# Thermal_MGT.net
KiCad netlist of a schematic drawn in Altium Designer
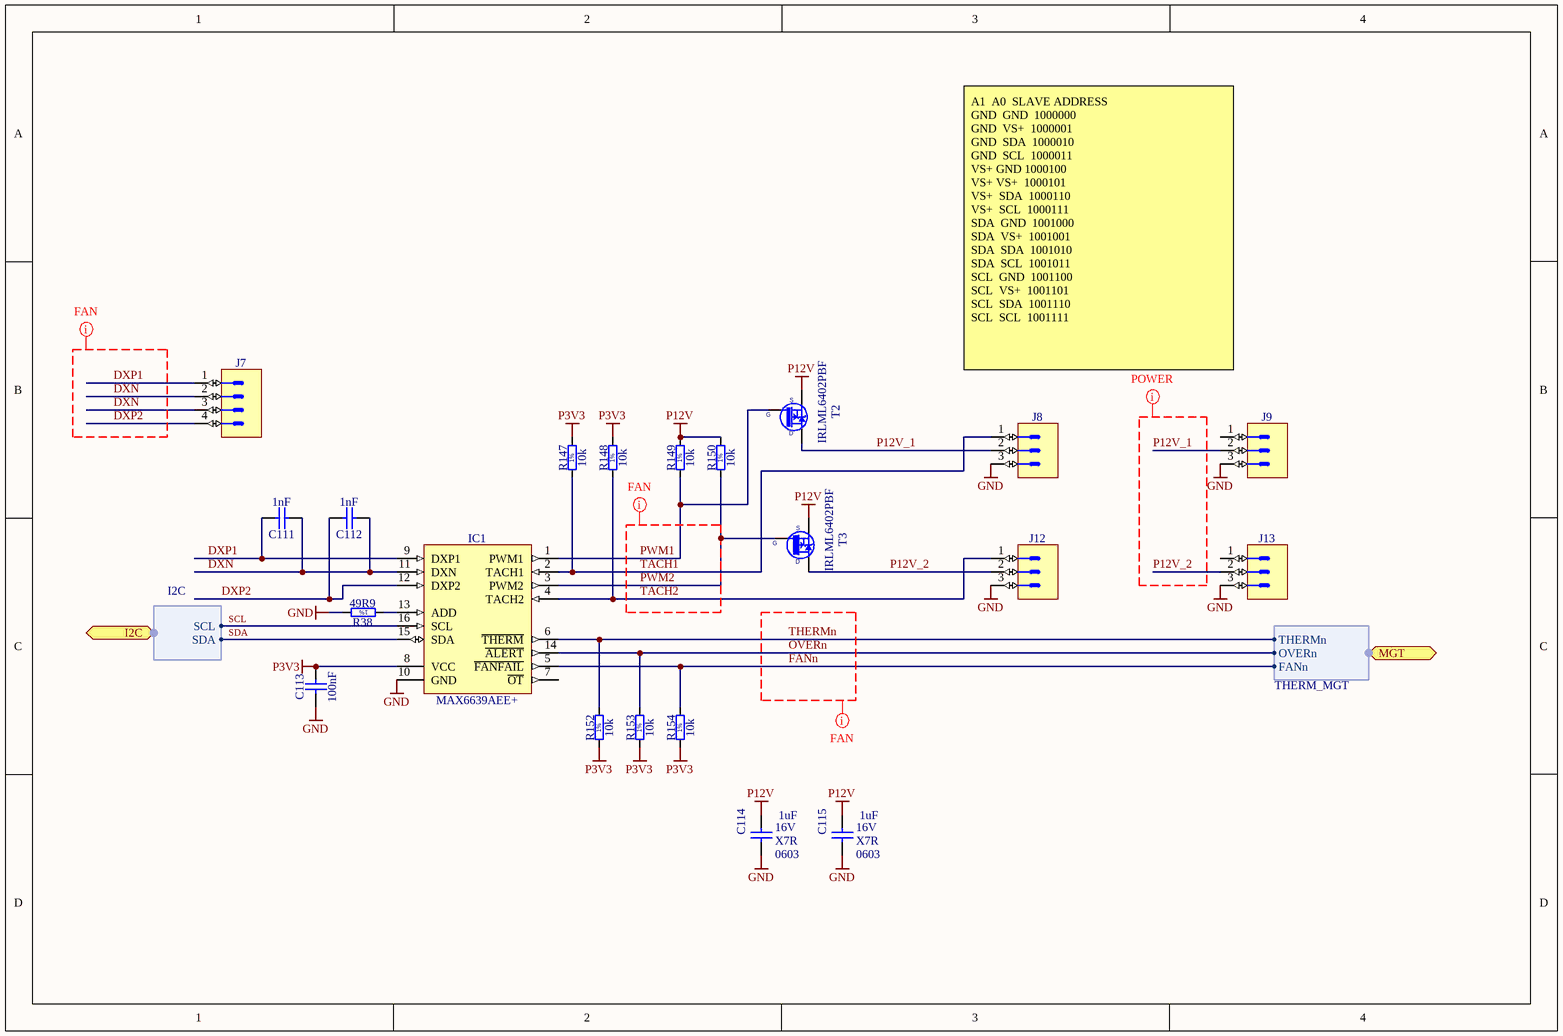
[diagram p0: Thermal_MGT.SchDoc]

(export (version "E")
  (design (tool "Eeschema 10.0.6"))
  (components
    (comp (ref "C111")
      (value "1nF")
      (footprint "CAPC1005X55N")
      (description "Non-polarised capacitor")
      (fields
        (field (name "PART NUMBER") "CC0402_1NF_50V_10%_X7R")
        (field (name "VOLTAGE") "50V")
        (field (name "AUTHOR") "CERN DEM JLC")
      )
      (libsource (lib "Capacitors") (part "Capacitor - non polarized"))
    )
    (comp (ref "C112")
      (value "1nF")
      (footprint "CAPC1005X55N")
      (description "Non-polarised capacitor")
      (fields
        (field (name "PART NUMBER") "CC0402_1NF_50V_10%_X7R")
        (field (name "VOLTAGE") "50V")
        (field (name "AUTHOR") "CERN DEM JLC")
      )
      (libsource (lib "Capacitors") (part "Capacitor - non polarized"))
    )
    (comp (ref "C113")
      (value "100nF")
      (footprint "CAPC1005X55N")
      (description "Non-polarised capacitor")
      (fields
        (field (name "PART NUMBER") "CC0402_100NF_16V_10%_X5R")
        (field (name "VOLTAGE") "16V")
        (field (name "AUTHOR") "CERN DEM JLC")
      )
      (libsource (lib "Capacitors") (part "Capacitor - non polarized"))
    )
    (comp (ref "C114")
      (value "1uF")
      (footprint "CAPC1608X87N")
      (description "Non-polarised capacitor")
      (fields
        (field (name "PART NUMBER") "CC0603_1UF_16V_10%_X7R")
        (field (name "VOLTAGE") "16V")
        (field (name "TC") "X7R")
        (field (name "TOLERANCE") "±10%")
        (field (name "CASE") "0603")
        (field (name "AUTHOR") "CERN DEM JLC")
      )
      (libsource (lib "Capacitors") (part "Capacitor - non polarized"))
    )
    (comp (ref "C115")
      (value "1uF")
      (footprint "CAPC1608X87N")
      (description "Non-polarised capacitor")
      (fields
        (field (name "PART NUMBER") "CC0603_1UF_16V_10%_X7R")
        (field (name "VOLTAGE") "16V")
        (field (name "TC") "X7R")
        (field (name "TOLERANCE") "±10%")
        (field (name "CASE") "0603")
        (field (name "AUTHOR") "CERN DEM JLC")
      )
      (libsource (lib "Capacitors") (part "Capacitor - non polarized"))
    )
    (comp (ref "IC1")
      (value "MAX6639AEE+")
      (footprint "SOP63P600X175-16N")
      (description "2-Channel Temperature Monitor with Dual, Automatic, PWM Fan-Speed Controller")
      (fields (field (name "MANUFACTURER") "MAXIM") (field (name "AUTHOR") "CERN DEM JLC"))
      (libsource (lib "ICs And Semiconductors") (part "MAX6639AEE+"))
    )
    (comp (ref "J7")
      (value "KK®")
      (footprint "MOLEX_22-27-2041")
      (description "Connector 4 Male")
      (fields
        (field (name "PART NUMBER") "MOLEX_22-27-2041")
        (field (name "MANUFACTURER") "MOLEX")
        (field (name "AUTHOR") "CERN DEM JLC")
      )
      (libsource (lib "Connectors") (part "Connector 4 Male"))
    )
    (comp (ref "J8")
      (value "KK®")
      (footprint "MOLEX_22-05-7038")
      (description "Connector 3 Male")
      (fields
        (field (name "PART NUMBER") "MOLEX_22-05-7038")
        (field (name "MANUFACTURER") "MOLEX")
        (field (name "AUTHOR") "CERN DEM JLC")
      )
      (libsource (lib "Connectors") (part "Connector 3 Male"))
    )
    (comp (ref "J9")
      (value "KK®")
      (footprint "MOLEX_22-05-7038")
      (description "Connector 3 Male")
      (fields
        (field (name "PART NUMBER") "MOLEX_22-05-7038")
        (field (name "MANUFACTURER") "MOLEX")
        (field (name "AUTHOR") "CERN DEM JLC")
      )
      (libsource (lib "Connectors") (part "Connector 3 Male"))
    )
    (comp (ref "J12")
      (value "KK®")
      (footprint "MOLEX_22-05-7038")
      (description "Connector 3 Male")
      (fields
        (field (name "PART NUMBER") "MOLEX_22-05-7038")
        (field (name "MANUFACTURER") "MOLEX")
        (field (name "AUTHOR") "CERN DEM JLC")
      )
      (libsource (lib "Connectors") (part "Connector 3 Male"))
    )
    (comp (ref "J13")
      (value "KK®")
      (footprint "MOLEX_22-05-7038")
      (description "Connector 3 Male")
      (fields
        (field (name "PART NUMBER") "MOLEX_22-05-7038")
        (field (name "MANUFACTURER") "MOLEX")
        (field (name "AUTHOR") "CERN DEM JLC")
      )
      (libsource (lib "Connectors") (part "Connector 3 Male"))
    )
    (comp (ref "R38")
      (value "49R9")
      (footprint "RESC1005X40N")
      (description "Resistor - 1%")
      (fields
        (field (name "PART NUMBER") "R0402_49R9_1%_0.0625W_100PPM")
        (field (name "POWER") "0.0625W")
        (field (name "AUTHOR") "CERN DEM JLC")
      )
      (libsource (lib "Resistors") (part "Resistor - 1%"))
    )
    (comp (ref "R147")
      (value "10k")
      (footprint "RESC1005X40N")
      (description "Resistor - 1%")
      (fields
        (field (name "PART NUMBER") "R0402_10K_1%_0.0625W_100PPM")
        (field (name "POWER") "0.0625W")
        (field (name "AUTHOR") "CERN DEM JLC")
      )
      (libsource (lib "Resistors") (part "Resistor - 1%"))
    )
    (comp (ref "R148")
      (value "10k")
      (footprint "RESC1005X40N")
      (description "Resistor - 1%")
      (fields
        (field (name "PART NUMBER") "R0402_10K_1%_0.0625W_100PPM")
        (field (name "POWER") "0.0625W")
        (field (name "AUTHOR") "CERN DEM JLC")
      )
      (libsource (lib "Resistors") (part "Resistor - 1%"))
    )
    (comp (ref "R149")
      (value "10k")
      (footprint "RESC1005X40N")
      (description "Resistor - 1%")
      (fields
        (field (name "PART NUMBER") "R0402_10K_1%_0.0625W_100PPM")
        (field (name "POWER") "0.0625W")
        (field (name "AUTHOR") "CERN DEM JLC")
      )
      (libsource (lib "Resistors") (part "Resistor - 1%"))
    )
    (comp (ref "R150")
      (value "10k")
      (footprint "RESC1005X40N")
      (description "Resistor - 1%")
      (fields
        (field (name "PART NUMBER") "R0402_10K_1%_0.0625W_100PPM")
        (field (name "POWER") "0.0625W")
        (field (name "AUTHOR") "CERN DEM JLC")
      )
      (libsource (lib "Resistors") (part "Resistor - 1%"))
    )
    (comp (ref "R152")
      (value "10k")
      (footprint "RESC1005X40N")
      (description "Resistor - 1%")
      (fields
        (field (name "PART NUMBER") "R0402_10K_1%_0.0625W_100PPM")
        (field (name "POWER") "0.0625W")
        (field (name "AUTHOR") "CERN DEM JLC")
      )
      (libsource (lib "Resistors") (part "Resistor - 1%"))
    )
    (comp (ref "R153")
      (value "10k")
      (footprint "RESC1005X40N")
      (description "Resistor - 1%")
      (fields
        (field (name "PART NUMBER") "R0402_10K_1%_0.0625W_100PPM")
        (field (name "POWER") "0.0625W")
        (field (name "AUTHOR") "CERN DEM JLC")
      )
      (libsource (lib "Resistors") (part "Resistor - 1%"))
    )
    (comp (ref "R154")
      (value "10k")
      (footprint "RESC1005X40N")
      (description "Resistor - 1%")
      (fields
        (field (name "PART NUMBER") "R0402_10K_1%_0.0625W_100PPM")
        (field (name "POWER") "0.0625W")
        (field (name "AUTHOR") "CERN DEM JLC")
      )
      (libsource (lib "Resistors") (part "Resistor - 1%"))
    )
    (comp (ref "T2")
      (value "IRLML6402PBF")
      (footprint "SOT95P237X112-3N")
      (description "P-CHANNEL MOSFET WITH ZENER DIODE")
      (fields (field (name "MANUFACTURER") "INTERNATIONAL RECTIFIER") (field (name "AUTHOR") "CERN DEM JLC"))
      (libsource (lib "ICs And Semiconductors") (part "P-MOSFET-DZ 1G 2S 3D"))
    )
    (comp (ref "T3")
      (value "IRLML6402PBF")
      (footprint "SOT95P237X112-3N")
      (description "P-CHANNEL MOSFET WITH ZENER DIODE")
      (fields (field (name "MANUFACTURER") "INTERNATIONAL RECTIFIER") (field (name "AUTHOR") "CERN DEM JLC"))
      (libsource (lib "ICs And Semiconductors") (part "P-MOSFET-DZ 1G 2S 3D"))
    )
  )
  (nets
    (net (code "3") (name "/DXN") (class "Default")
      (node (ref "C111") (pin "1") (pinfunction "1_1") (pintype "passive"))
      (node (ref "C112") (pin "1") (pinfunction "1_1") (pintype "passive"))
      (node (ref "IC1") (pin "11") (pinfunction "DXN_11") (pintype "input"))
      (node (ref "J7") (pin "2") (pinfunction "2_2") (pintype "bidirectional"))
      (node (ref "J7") (pin "3") (pinfunction "3_3") (pintype "bidirectional"))
    )
    (net (code "4") (name "/DXP1") (class "Default")
      (node (ref "C111") (pin "2") (pinfunction "2_2") (pintype "passive"))
      (node (ref "IC1") (pin "9") (pinfunction "DXP1_9") (pintype "input"))
      (node (ref "J7") (pin "1") (pinfunction "1_1") (pintype "bidirectional"))
    )
    (net (code "5") (name "/DXP2") (class "Default")
      (node (ref "C112") (pin "2") (pinfunction "2_2") (pintype "passive"))
      (node (ref "IC1") (pin "12") (pinfunction "DXP2_12") (pintype "input"))
      (node (ref "J7") (pin "4") (pinfunction "4_4") (pintype "bidirectional"))
    )
    (net (code "6") (name "/FANn") (class "Default")
      (node (ref "IC1") (pin "5") (pinfunction "~{FANFAIL}_5") (pintype "output"))
      (node (ref "R154") (pin "2") (pinfunction "2_2") (pintype "passive"))
    )
    (net (code "7") (name "/OVERn") (class "Default")
      (node (ref "IC1") (pin "14") (pinfunction "~{ALERT}_14") (pintype "output"))
      (node (ref "R153") (pin "2") (pinfunction "2_2") (pintype "passive"))
    )
    (net (code "8") (name "/P12V_1") (class "Default")
      (node (ref "J8") (pin "2") (pinfunction "2_2") (pintype "bidirectional"))
      (node (ref "J9") (pin "2") (pinfunction "2_2") (pintype "bidirectional"))
      (node (ref "T2") (pin "3") (pinfunction "D_3") (pintype "passive"))
    )
    (net (code "9") (name "/P12V_2") (class "Default")
      (node (ref "J12") (pin "2") (pinfunction "2_2") (pintype "bidirectional"))
      (node (ref "J13") (pin "2") (pinfunction "2_2") (pintype "bidirectional"))
      (node (ref "T3") (pin "3") (pinfunction "D_3") (pintype "passive"))
    )
    (net (code "10") (name "/PWM1") (class "Default")
      (node (ref "IC1") (pin "1") (pinfunction "PWM1_1") (pintype "output"))
      (node (ref "R149") (pin "1") (pinfunction "1_1") (pintype "passive"))
      (node (ref "T2") (pin "1") (pinfunction "G_1") (pintype "passive"))
    )
    (net (code "11") (name "/PWM2") (class "Default")
      (node (ref "IC1") (pin "3") (pinfunction "PWM2_3") (pintype "output"))
      (node (ref "R150") (pin "1") (pinfunction "1_1") (pintype "passive"))
      (node (ref "T3") (pin "1") (pinfunction "G_1") (pintype "passive"))
    )
    (net (code "12") (name "/SCL") (class "Default")
      (node (ref "IC1") (pin "16") (pinfunction "SCL_16") (pintype "input"))
    )
    (net (code "13") (name "/SDA") (class "Default")
      (node (ref "IC1") (pin "15") (pinfunction "SDA_15") (pintype "bidirectional"))
    )
    (net (code "14") (name "/TACH1") (class "Default")
      (node (ref "IC1") (pin "2") (pinfunction "TACH1_2") (pintype "input"))
      (node (ref "J8") (pin "1") (pinfunction "1_1") (pintype "bidirectional"))
      (node (ref "R147") (pin "1") (pinfunction "1_1") (pintype "passive"))
    )
    (net (code "15") (name "/TACH2") (class "Default")
      (node (ref "IC1") (pin "4") (pinfunction "TACH2_4") (pintype "input"))
      (node (ref "J12") (pin "1") (pinfunction "1_1") (pintype "bidirectional"))
      (node (ref "R148") (pin "1") (pinfunction "1_1") (pintype "passive"))
    )
    (net (code "16") (name "/THERMn") (class "Default")
      (node (ref "IC1") (pin "6") (pinfunction "~{THERM}_6") (pintype "output"))
      (node (ref "R152") (pin "2") (pinfunction "2_2") (pintype "passive"))
    )
    (net (code "19") (name "GND") (class "Default")
      (node (ref "C113") (pin "1") (pinfunction "1_1") (pintype "passive"))
      (node (ref "C114") (pin "1") (pinfunction "1_1") (pintype "passive"))
      (node (ref "C115") (pin "1") (pinfunction "1_1") (pintype "passive"))
      (node (ref "IC1") (pin "10") (pinfunction "GND_10") (pintype "power_in"))
      (node (ref "J12") (pin "3") (pinfunction "3_3") (pintype "bidirectional"))
      (node (ref "J13") (pin "3") (pinfunction "3_3") (pintype "bidirectional"))
      (node (ref "J8") (pin "3") (pinfunction "3_3") (pintype "bidirectional"))
      (node (ref "J9") (pin "3") (pinfunction "3_3") (pintype "bidirectional"))
      (node (ref "R38") (pin "2") (pinfunction "2_2") (pintype "passive"))
    )
    (net (code "20") (name "Net-(IC1-ADD)") (class "Default")
      (node (ref "IC1") (pin "13") (pinfunction "ADD_13") (pintype "input"))
      (node (ref "R38") (pin "1") (pinfunction "1_1") (pintype "passive"))
    )
    (net (code "21") (name "P3V3") (class "Default")
      (node (ref "C113") (pin "2") (pinfunction "2_2") (pintype "passive"))
      (node (ref "IC1") (pin "8") (pinfunction "VCC_8") (pintype "power_in"))
      (node (ref "R147") (pin "2") (pinfunction "2_2") (pintype "passive"))
      (node (ref "R148") (pin "2") (pinfunction "2_2") (pintype "passive"))
      (node (ref "R152") (pin "1") (pinfunction "1_1") (pintype "passive"))
      (node (ref "R153") (pin "1") (pinfunction "1_1") (pintype "passive"))
      (node (ref "R154") (pin "1") (pinfunction "1_1") (pintype "passive"))
    )
    (net (code "22") (name "P12V") (class "Default")
      (node (ref "C114") (pin "2") (pinfunction "2_2") (pintype "passive"))
      (node (ref "C115") (pin "2") (pinfunction "2_2") (pintype "passive"))
      (node (ref "R149") (pin "2") (pinfunction "2_2") (pintype "passive"))
      (node (ref "R150") (pin "2") (pinfunction "2_2") (pintype "passive"))
      (node (ref "T2") (pin "2") (pinfunction "S_2") (pintype "passive"))
      (node (ref "T3") (pin "2") (pinfunction "S_2") (pintype "passive"))
    )
    (net (code "23") (name "unconnected-(IC1-~{OT}-Pad7)") (class "Default")
      (node (ref "IC1") (pin "7") (pinfunction "~{OT}_7") (pintype "output"))
    )
    (net (code "24") (name "unconnected-(J9-Pad1)") (class "Default")
      (node (ref "J9") (pin "1") (pinfunction "1_1") (pintype "bidirectional"))
    )
    (net (code "25") (name "unconnected-(J13-Pad1)") (class "Default")
      (node (ref "J13") (pin "1") (pinfunction "1_1") (pintype "bidirectional"))
    )
  )
)
